# HR-Autoflat.net
KiCad netlist of a schematic drawn in Altium Designer
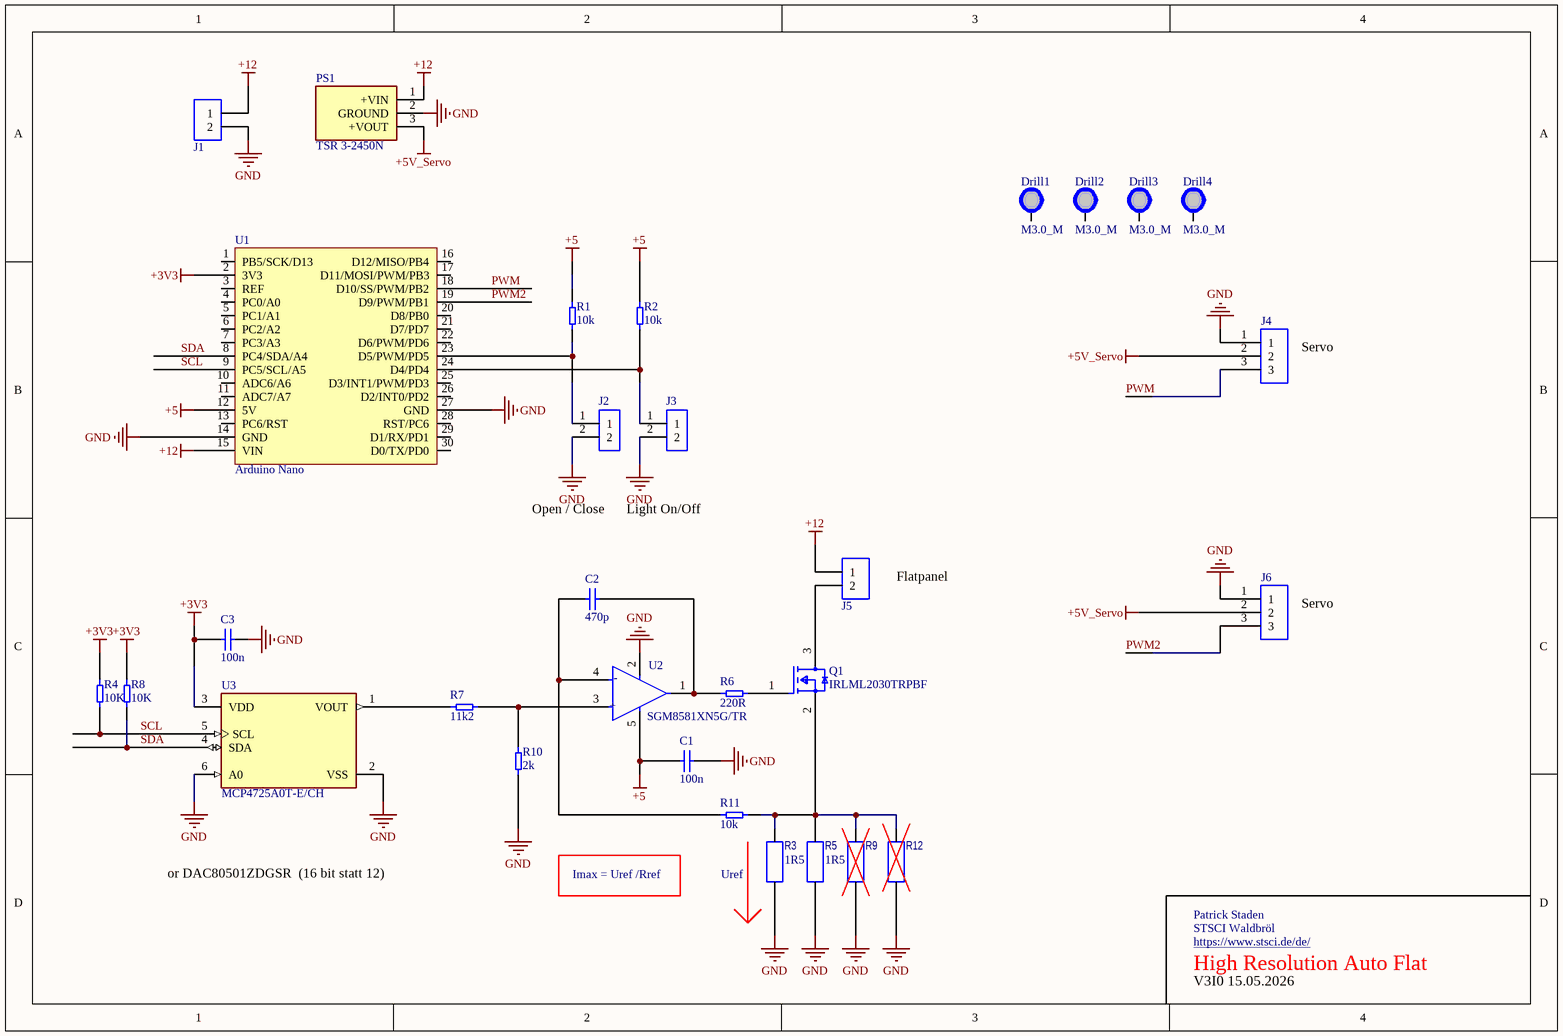
[diagram p0: HR-Autoflat.SchDoc]

(export (version "E")
  (design (tool "Eeschema 10.0.6"))
  (components
    (comp (ref "C1")
      (value "100n")
      (footprint "C0603_L")
      (fields
        (field (name "PUBLISHER") "Altium Limited")
        (field (name ".CHECKED PCB") "RF")
        (field (name ".CHECKED SCH") "RF")
      )
      (libsource (lib "Passive Bauelemente") (part "C0603"))
    )
    (comp (ref "C2")
      (value "470p")
      (footprint "C0603_L")
      (fields
        (field (name "PUBLISHER") "Altium Limited")
        (field (name ".CHECKED PCB") "RF")
        (field (name ".CHECKED SCH") "RF")
      )
      (libsource (lib "Passive Bauelemente") (part "C0603"))
    )
    (comp (ref "C3")
      (value "100n")
      (footprint "C0603_L")
      (fields
        (field (name "PUBLISHER") "Altium Limited")
        (field (name ".CHECKED PCB") "RF")
        (field (name ".CHECKED SCH") "RF")
      )
      (libsource (lib "Passive Bauelemente") (part "C0603"))
    )
    (comp (ref "Drill1")
      (value "M3.0_M")
      (footprint "M3.0_M")
      (fields (field (name ".CHECKED PCB") "RF") (field (name ".CHECKED SCH") "RF"))
      (libsource (lib "Drills") (part "Drill"))
    )
    (comp (ref "Drill2")
      (value "M3.0_M")
      (footprint "M3.0_M")
      (fields (field (name ".CHECKED PCB") "RF") (field (name ".CHECKED SCH") "RF"))
      (libsource (lib "Drills") (part "Drill"))
    )
    (comp (ref "Drill3")
      (value "M3.0_M")
      (footprint "M3.0_M")
      (fields (field (name ".CHECKED PCB") "RF") (field (name ".CHECKED SCH") "RF"))
      (libsource (lib "Drills") (part "Drill"))
    )
    (comp (ref "Drill4")
      (value "M3.0_M")
      (footprint "M3.0_M")
      (fields (field (name ".CHECKED PCB") "RF") (field (name ".CHECKED SCH") "RF"))
      (libsource (lib "Drills") (part "Drill"))
    )
    (comp (ref "J1")
      (value "PM_5.08_3_90_3.5_SW_-176052000")
      (footprint "MKDSN 5,08/2 2,5")
      (description "间距5.08mm 2pin 10A 300V 可拼接 螺钉式 直插 配线24-14AWG(0.2-2.5)mm²")
      (fields
        (field (name "MANUFACTURER") "Phoenix Contact")
        (field (name "MANUFACTURER PART NUMBER") "1888687")
        (field (name ".CHECKED PCB") "PS")
        (field (name ".CHECKED SCH") "PS")
      )
      (libsource (lib "Phoenix Contact") (part "MKDSN 5,08/2 2,5"))
    )
    (comp (ref "J2")
      (value "896-7620")
      (footprint "2P Stiftleiste 2,54 mm")
      (fields
        (field (name "MANUFACTURER_PART_NUMBER") "42375-0002")
        (field (name ".CHECKED PCB") "RF")
        (field (name ".CHECKED SCH") "RF")
      )
      (libsource (lib "EigenDefault") (part "2P Stiftleiste 2,54"))
    )
    (comp (ref "J3")
      (value "896-7620")
      (footprint "2P Stiftleiste 2,54 mm")
      (fields
        (field (name "MANUFACTURER_PART_NUMBER") "42375-0002")
        (field (name ".CHECKED PCB") "RF")
        (field (name ".CHECKED SCH") "RF")
      )
      (libsource (lib "EigenDefault") (part "2P Stiftleiste 2,54"))
    )
    (comp (ref "J4")
      (value "251-8092")
      (footprint "3P Stiftleiste 2,54 mm")
      (fields (field (name ".CHECKED PCB") "RF") (field (name ".CHECKED SCH") "RF"))
      (libsource (lib "EigenDefault") (part "3P Stiftleiste 2,54"))
    )
    (comp (ref "J5")
      (value "PM_5.08_3_90_3.5_SW_-176052000")
      (footprint "MKDSN 5,08/2 2,5")
      (description "间距5.08mm 2pin 10A 300V 可拼接 螺钉式 直插 配线24-14AWG(0.2-2.5)mm²")
      (fields
        (field (name "MANUFACTURER") "Phoenix Contact")
        (field (name "MANUFACTURER PART NUMBER") "1888687")
        (field (name ".CHECKED PCB") "PS")
        (field (name ".CHECKED SCH") "PS")
      )
      (libsource (lib "Phoenix Contact") (part "MKDSN 5,08/2 2,5"))
    )
    (comp (ref "J6")
      (value "251-8092")
      (footprint "3P Stiftleiste 2,54 mm")
      (fields (field (name ".CHECKED PCB") "RF") (field (name ".CHECKED SCH") "RF"))
      (libsource (lib "EigenDefault") (part "3P Stiftleiste 2,54"))
    )
    (comp (ref "PS1")
      (value "TSR 3-2450N")
      (footprint "SamacSys:TSR324120N")
      (description "or TSR 3-2450N")
      (libsource (lib "*") (part "TSR_3-24120N"))
    )
    (comp (ref "Q1")
      (value "IRLML2030TRPBF")
      (footprint "FP-Micro3-MFG")
      (description "MOSFET N-CH 30V 2.7A SOT-23-3")
      (fields
        (field (name "OCTOPART") "https://octopart.com/irlml2030trpbf-infineon-65874966")
        (field (name "MANUFACTURER") "Infineon")
      )
      (libsource (lib "Altium Content Vault") (part "0a9ea7c96deaaede766a5b531c28de0"))
    )
    (comp (ref "R1")
      (value "10k")
      (footprint "R0603_M")
      (fields
        (field (name "POWER") "35 W")
        (field (name "PUBLISHER") "Altium Limited")
        (field (name ".CHECKED PCB") "RF")
        (field (name ".CHECKED SCH") "RF")
      )
      (libsource (lib "Passive Bauelemente") (part "R0603"))
    )
    (comp (ref "R2")
      (value "10k")
      (footprint "R0603_M")
      (fields
        (field (name "POWER") "35 W")
        (field (name "PUBLISHER") "Altium Limited")
        (field (name ".CHECKED PCB") "RF")
        (field (name ".CHECKED SCH") "RF")
      )
      (libsource (lib "Passive Bauelemente") (part "R0603"))
    )
    (comp (ref "R3")
      (value "1R5")
      (footprint "R 0.125W V P2.54")
      (description "Ind Power 180uH 10% 1KHz Ferrite 380mA Axial T/R")
      (fields
        (field (name "MANUFACTURER") "Abracon")
        (field (name "MANUFACTURER PART NUMBER") "AIAP-01-181K-T")
      )
      (libsource (lib "Resistor") (part "Resistor RU"))
    )
    (comp (ref "R4")
      (value "10K")
      (footprint "R0805_M")
      (fields
        (field (name "POWER") "35 W")
        (field (name "PUBLISHER") "Altium Limited")
        (field (name ".CHECKED PCB") "RF")
        (field (name ".CHECKED SCH") "RF")
      )
      (libsource (lib "Passive Bauelemente") (part "R0805"))
    )
    (comp (ref "R5")
      (value "1R5")
      (footprint "R 0.125W V P2.54")
      (description "Ind Power 180uH 10% 1KHz Ferrite 380mA Axial T/R")
      (fields
        (field (name "MANUFACTURER") "Abracon")
        (field (name "MANUFACTURER PART NUMBER") "AIAP-01-181K-T")
      )
      (libsource (lib "Resistor") (part "Resistor RU"))
    )
    (comp (ref "R6")
      (value "220R")
      (footprint "R0603_M")
      (fields
        (field (name "POWER") "35 W")
        (field (name "PUBLISHER") "Altium Limited")
        (field (name ".CHECKED PCB") "RF")
        (field (name ".CHECKED SCH") "RF")
      )
      (libsource (lib "Passive Bauelemente") (part "R0603"))
    )
    (comp (ref "R7")
      (value "11k2")
      (footprint "R0603_M")
      (fields
        (field (name "POWER") "35 W")
        (field (name "PUBLISHER") "Altium Limited")
        (field (name ".CHECKED PCB") "RF")
        (field (name ".CHECKED SCH") "RF")
      )
      (libsource (lib "Passive Bauelemente") (part "R0603"))
    )
    (comp (ref "R8")
      (value "10K")
      (footprint "R0805_M")
      (fields
        (field (name "POWER") "35 W")
        (field (name "PUBLISHER") "Altium Limited")
        (field (name ".CHECKED PCB") "RF")
        (field (name ".CHECKED SCH") "RF")
      )
      (libsource (lib "Passive Bauelemente") (part "R0805"))
    )
    (comp (ref "R9")
      (value "1R4")
      (footprint "R 0.125W V P2.54")
      (description "Ind Power 180uH 10% 1KHz Ferrite 380mA Axial T/R")
      (fields
        (field (name "MANUFACTURER") "Abracon")
        (field (name "MANUFACTURER PART NUMBER") "AIAP-01-181K-T")
      )
      (libsource (lib "Resistor") (part "Resistor RU"))
    )
    (comp (ref "R10")
      (value "2k")
      (footprint "R0603_M")
      (fields
        (field (name "POWER") "35 W")
        (field (name "PUBLISHER") "Altium Limited")
        (field (name ".CHECKED PCB") "RF")
        (field (name ".CHECKED SCH") "RF")
      )
      (libsource (lib "Passive Bauelemente") (part "R0603"))
    )
    (comp (ref "R11")
      (value "10k")
      (footprint "R0603_M")
      (fields
        (field (name "POWER") "35 W")
        (field (name "PUBLISHER") "Altium Limited")
        (field (name ".CHECKED PCB") "RF")
        (field (name ".CHECKED SCH") "RF")
      )
      (libsource (lib "Passive Bauelemente") (part "R0603"))
    )
    (comp (ref "R12")
      (value "1R4")
      (footprint "R 0.125W V P2.54")
      (description "Ind Power 180uH 10% 1KHz Ferrite 380mA Axial T/R")
      (fields
        (field (name "MANUFACTURER") "Abracon")
        (field (name "MANUFACTURER PART NUMBER") "AIAP-01-181K-T")
      )
      (libsource (lib "Resistor") (part "Resistor RU"))
    )
    (comp (ref "U1")
      (value "Arduino Nano")
      (footprint "Arduino Nano")
      (description "Nano Every Development Brd, 8Bit Avr Mcu Rohs Compliant: Yes")
      (fields
        (field (name "MANUFACTURER") "Arduino")
        (field (name "MANUFACTURER PART NUMBER") "ABX00028")
        (field (name ".SCH CHECKED") "PS")
        (field (name ".PCB CHECKED") "PS")
      )
      (libsource (lib "Arduino System") (part "Arduino Nano"))
    )
    (comp (ref "U2")
      (value "SGM8581XN5G/TR")
      (footprint "AutoFlat:FP-C04-091-OT-MFG")
      (libsource (lib "AutoFlat") (part "SOT-23-5"))
    )
    (comp (ref "U3")
      (value "MCP4725A0T-E/CH")
      (footprint "FP-C04-028-CHY-IPC_A")
      (description "IC DAC 12BIT V-OUT SOT23-6")
      (libsource (lib "Altium Content Vault") (part "13d1b9b03173b6bd00baa384b893ce8"))
    )
  )
  (nets
    (net (code "1") (name "+3V3") (class "Default")
      (node (ref "C3") (pin "1") (pinfunction "1_1") (pintype "passive"))
      (node (ref "R4") (pin "2") (pinfunction "2_2") (pintype "passive"))
      (node (ref "R8") (pin "2") (pinfunction "2_2") (pintype "passive"))
      (node (ref "U1") (pin "2") (pinfunction "3V3_2") (pintype "passive"))
      (node (ref "U3") (pin "3") (pinfunction "VDD_3") (pintype "power_in"))
    )
    (net (code "2") (name "+5") (class "Default")
      (node (ref "C1") (pin "1") (pinfunction "1_1") (pintype "passive"))
      (node (ref "R1") (pin "2") (pinfunction "2_2") (pintype "passive"))
      (node (ref "R2") (pin "2") (pinfunction "2_2") (pintype "passive"))
      (node (ref "U1") (pin "12") (pinfunction "5V_12") (pintype "passive"))
      (node (ref "U2") (pin "5") (pinfunction "VDD_5") (pintype "passive"))
    )
    (net (code "3") (name "+5V_Servo") (class "Default")
      (node (ref "J4") (pin "2") (pinfunction "2_2") (pintype "passive"))
      (node (ref "J6") (pin "2") (pinfunction "2_2") (pintype "passive"))
      (node (ref "PS1") (pin "3") (pinfunction "+VOUT_3") (pintype "passive"))
    )
    (net (code "4") (name "+12") (class "Default")
      (node (ref "J1") (pin "1") (pinfunction "1_1") (pintype "passive"))
      (node (ref "J5") (pin "1") (pinfunction "1_1") (pintype "passive"))
      (node (ref "PS1") (pin "1") (pinfunction "+VIN_1") (pintype "passive"))
      (node (ref "U1") (pin "15") (pinfunction "VIN_15") (pintype "passive"))
    )
    (net (code "5") (name "/PWM") (class "Default")
      (node (ref "J4") (pin "3") (pinfunction "3_3") (pintype "passive"))
      (node (ref "U1") (pin "18") (pinfunction "D10/SS/PWM/PB2_18") (pintype "passive"))
    )
    (net (code "6") (name "/PWM2") (class "Default")
      (node (ref "J6") (pin "3") (pinfunction "3_3") (pintype "passive"))
      (node (ref "U1") (pin "19") (pinfunction "D9/PWM/PB1_19") (pintype "passive"))
    )
    (net (code "7") (name "/SCL") (class "Default")
      (node (ref "R4") (pin "1") (pinfunction "1_1") (pintype "passive"))
      (node (ref "U1") (pin "9") (pinfunction "PC5/SCL/A5_9") (pintype "passive"))
      (node (ref "U3") (pin "5") (pinfunction "SCL_5") (pintype "input"))
    )
    (net (code "8") (name "/SDA") (class "Default")
      (node (ref "R8") (pin "1") (pinfunction "1_1") (pintype "passive"))
      (node (ref "U1") (pin "8") (pinfunction "PC4/SDA/A4_8") (pintype "passive"))
      (node (ref "U3") (pin "4") (pinfunction "SDA_4") (pintype "bidirectional"))
    )
    (net (code "9") (name "GND") (class "Default")
      (node (ref "C1") (pin "2") (pinfunction "2_2") (pintype "passive"))
      (node (ref "C3") (pin "2") (pinfunction "2_2") (pintype "passive"))
      (node (ref "J1") (pin "2") (pinfunction "2_2") (pintype "passive"))
      (node (ref "J2") (pin "2") (pinfunction "2_2") (pintype "passive"))
      (node (ref "J3") (pin "2") (pinfunction "2_2") (pintype "passive"))
      (node (ref "J4") (pin "1") (pinfunction "1_1") (pintype "passive"))
      (node (ref "J6") (pin "1") (pinfunction "1_1") (pintype "passive"))
      (node (ref "PS1") (pin "2") (pinfunction "GROUND_2") (pintype "passive"))
      (node (ref "R10") (pin "1") (pinfunction "1_1") (pintype "passive"))
      (node (ref "R12") (pin "1") (pinfunction "1_1") (pintype "passive"))
      (node (ref "R3") (pin "1") (pinfunction "1_1") (pintype "passive"))
      (node (ref "R5") (pin "1") (pinfunction "1_1") (pintype "passive"))
      (node (ref "R9") (pin "1") (pinfunction "1_1") (pintype "passive"))
      (node (ref "U1") (pin "14") (pinfunction "GND_14") (pintype "passive"))
      (node (ref "U1") (pin "27") (pinfunction "GND_27") (pintype "passive"))
      (node (ref "U2") (pin "2") (pinfunction "VSS_2") (pintype "passive"))
      (node (ref "U3") (pin "2") (pinfunction "VSS_2") (pintype "power_in"))
      (node (ref "U3") (pin "6") (pinfunction "A0_6") (pintype "input"))
    )
    (net (code "10") (name "Net-(Q1-D)") (class "Default")
      (node (ref "J5") (pin "2") (pinfunction "2_2") (pintype "passive"))
      (node (ref "Q1") (pin "3") (pinfunction "D_3") (pintype "passive"))
    )
    (net (code "11") (name "Net-(Q1-G)") (class "Default")
      (node (ref "Q1") (pin "1") (pinfunction "G_1") (pintype "passive"))
      (node (ref "R6") (pin "2") (pinfunction "2_2") (pintype "passive"))
    )
    (net (code "12") (name "Net-(Q1-S)") (class "Default")
      (node (ref "Q1") (pin "2") (pinfunction "S_2") (pintype "passive"))
      (node (ref "R11") (pin "2") (pinfunction "2_2") (pintype "passive"))
      (node (ref "R12") (pin "2") (pinfunction "2_2") (pintype "passive"))
      (node (ref "R3") (pin "2") (pinfunction "2_2") (pintype "passive"))
      (node (ref "R5") (pin "2") (pinfunction "2_2") (pintype "passive"))
      (node (ref "R9") (pin "2") (pinfunction "2_2") (pintype "passive"))
    )
    (net (code "13") (name "Net-(U1-D4{slash}PD4)") (class "Default")
      (node (ref "J3") (pin "1") (pinfunction "1_1") (pintype "passive"))
      (node (ref "R2") (pin "1") (pinfunction "1_1") (pintype "passive"))
      (node (ref "U1") (pin "24") (pinfunction "D4/PD4_24") (pintype "passive"))
    )
    (net (code "14") (name "Net-(U1-D5{slash}PWM{slash}PD5)") (class "Default")
      (node (ref "J2") (pin "1") (pinfunction "1_1") (pintype "passive"))
      (node (ref "R1") (pin "1") (pinfunction "1_1") (pintype "passive"))
      (node (ref "U1") (pin "23") (pinfunction "D5/PWM/PD5_23") (pintype "passive"))
    )
    (net (code "15") (name "Net-(U2-VIN+)") (class "Default")
      (node (ref "R10") (pin "2") (pinfunction "2_2") (pintype "passive"))
      (node (ref "R7") (pin "2") (pinfunction "2_2") (pintype "passive"))
      (node (ref "U2") (pin "3") (pinfunction "VIN+_3") (pintype "passive"))
    )
    (net (code "16") (name "Net-(U2-VIN-)") (class "Default")
      (node (ref "C2") (pin "1") (pinfunction "1_1") (pintype "passive"))
      (node (ref "R11") (pin "1") (pinfunction "1_1") (pintype "passive"))
      (node (ref "U2") (pin "4") (pinfunction "VIN-_4") (pintype "passive"))
    )
    (net (code "17") (name "Net-(U2-VOUT)") (class "Default")
      (node (ref "C2") (pin "2") (pinfunction "2_2") (pintype "passive"))
      (node (ref "R6") (pin "1") (pinfunction "1_1") (pintype "passive"))
      (node (ref "U2") (pin "1") (pinfunction "VOUT_1") (pintype "passive"))
    )
    (net (code "18") (name "Net-(U3-VOUT)") (class "Default")
      (node (ref "R7") (pin "1") (pinfunction "1_1") (pintype "passive"))
      (node (ref "U3") (pin "1") (pinfunction "VOUT_1") (pintype "output"))
    )
    (net (code "19") (name "unconnected-(Drill1-Pad1)") (class "Default")
      (node (ref "Drill1") (pin "1") (pinfunction "1_1") (pintype "passive"))
    )
    (net (code "20") (name "unconnected-(Drill2-Pad1)") (class "Default")
      (node (ref "Drill2") (pin "1") (pinfunction "1_1") (pintype "passive"))
    )
    (net (code "21") (name "unconnected-(Drill3-Pad1)") (class "Default")
      (node (ref "Drill3") (pin "1") (pinfunction "1_1") (pintype "passive"))
    )
    (net (code "22") (name "unconnected-(Drill4-Pad1)") (class "Default")
      (node (ref "Drill4") (pin "1") (pinfunction "1_1") (pintype "passive"))
    )
    (net (code "23") (name "unconnected-(U1-ADC6{slash}A6-Pad10)") (class "Default")
      (node (ref "U1") (pin "10") (pinfunction "ADC6/A6_10") (pintype "passive"))
    )
    (net (code "24") (name "unconnected-(U1-ADC7{slash}A7-Pad11)") (class "Default")
      (node (ref "U1") (pin "11") (pinfunction "ADC7/A7_11") (pintype "passive"))
    )
    (net (code "25") (name "unconnected-(U1-D0{slash}TX{slash}PD0-Pad30)") (class "Default")
      (node (ref "U1") (pin "30") (pinfunction "D0/TX/PD0_30") (pintype "passive"))
    )
    (net (code "26") (name "unconnected-(U1-D1{slash}RX{slash}PD1-Pad29)") (class "Default")
      (node (ref "U1") (pin "29") (pinfunction "D1/RX/PD1_29") (pintype "passive"))
    )
    (net (code "27") (name "unconnected-(U1-D2{slash}INT0{slash}PD2-Pad26)") (class "Default")
      (node (ref "U1") (pin "26") (pinfunction "D2/INT0/PD2_26") (pintype "passive"))
    )
    (net (code "28") (name "unconnected-(U1-D3{slash}INT1{slash}PWM{slash}PD3-Pad25)") (class "Default")
      (node (ref "U1") (pin "25") (pinfunction "D3/INT1/PWM/PD3_25") (pintype "passive"))
    )
    (net (code "29") (name "unconnected-(U1-D6{slash}PWM{slash}PD6-Pad22)") (class "Default")
      (node (ref "U1") (pin "22") (pinfunction "D6/PWM/PD6_22") (pintype "passive"))
    )
    (net (code "30") (name "unconnected-(U1-D7{slash}PD7-Pad21)") (class "Default")
      (node (ref "U1") (pin "21") (pinfunction "D7/PD7_21") (pintype "passive"))
    )
    (net (code "31") (name "unconnected-(U1-D8{slash}PB0-Pad20)") (class "Default")
      (node (ref "U1") (pin "20") (pinfunction "D8/PB0_20") (pintype "passive"))
    )
    (net (code "32") (name "unconnected-(U1-D11{slash}MOSI{slash}PWM{slash}PB3-Pad17)") (class "Default")
      (node (ref "U1") (pin "17") (pinfunction "D11/MOSI/PWM/PB3_17") (pintype "passive"))
    )
    (net (code "33") (name "unconnected-(U1-D12{slash}MISO{slash}PB4-Pad16)") (class "Default")
      (node (ref "U1") (pin "16") (pinfunction "D12/MISO/PB4_16") (pintype "passive"))
    )
    (net (code "34") (name "unconnected-(U1-PB5{slash}SCK{slash}D13-Pad1)") (class "Default")
      (node (ref "U1") (pin "1") (pinfunction "PB5/SCK/D13_1") (pintype "passive"))
    )
    (net (code "35") (name "unconnected-(U1-PC0{slash}A0-Pad4)") (class "Default")
      (node (ref "U1") (pin "4") (pinfunction "PC0/A0_4") (pintype "passive"))
    )
    (net (code "36") (name "unconnected-(U1-PC1{slash}A1-Pad5)") (class "Default")
      (node (ref "U1") (pin "5") (pinfunction "PC1/A1_5") (pintype "passive"))
    )
    (net (code "37") (name "unconnected-(U1-PC2{slash}A2-Pad6)") (class "Default")
      (node (ref "U1") (pin "6") (pinfunction "PC2/A2_6") (pintype "passive"))
    )
    (net (code "38") (name "unconnected-(U1-PC3{slash}A3-Pad7)") (class "Default")
      (node (ref "U1") (pin "7") (pinfunction "PC3/A3_7") (pintype "passive"))
    )
    (net (code "39") (name "unconnected-(U1-PC6{slash}RST-Pad13)") (class "Default")
      (node (ref "U1") (pin "13") (pinfunction "PC6/RST_13") (pintype "passive"))
    )
    (net (code "40") (name "unconnected-(U1-REF-Pad3)") (class "Default")
      (node (ref "U1") (pin "3") (pinfunction "REF_3") (pintype "passive"))
    )
    (net (code "41") (name "unconnected-(U1-RST{slash}PC6-Pad28)") (class "Default")
      (node (ref "U1") (pin "28") (pinfunction "RST/PC6_28") (pintype "passive"))
    )
  )
)
